# SparkFun_Soil_Moisture_Sensor.net
KiCad netlist of a schematic drawn in EAGLE
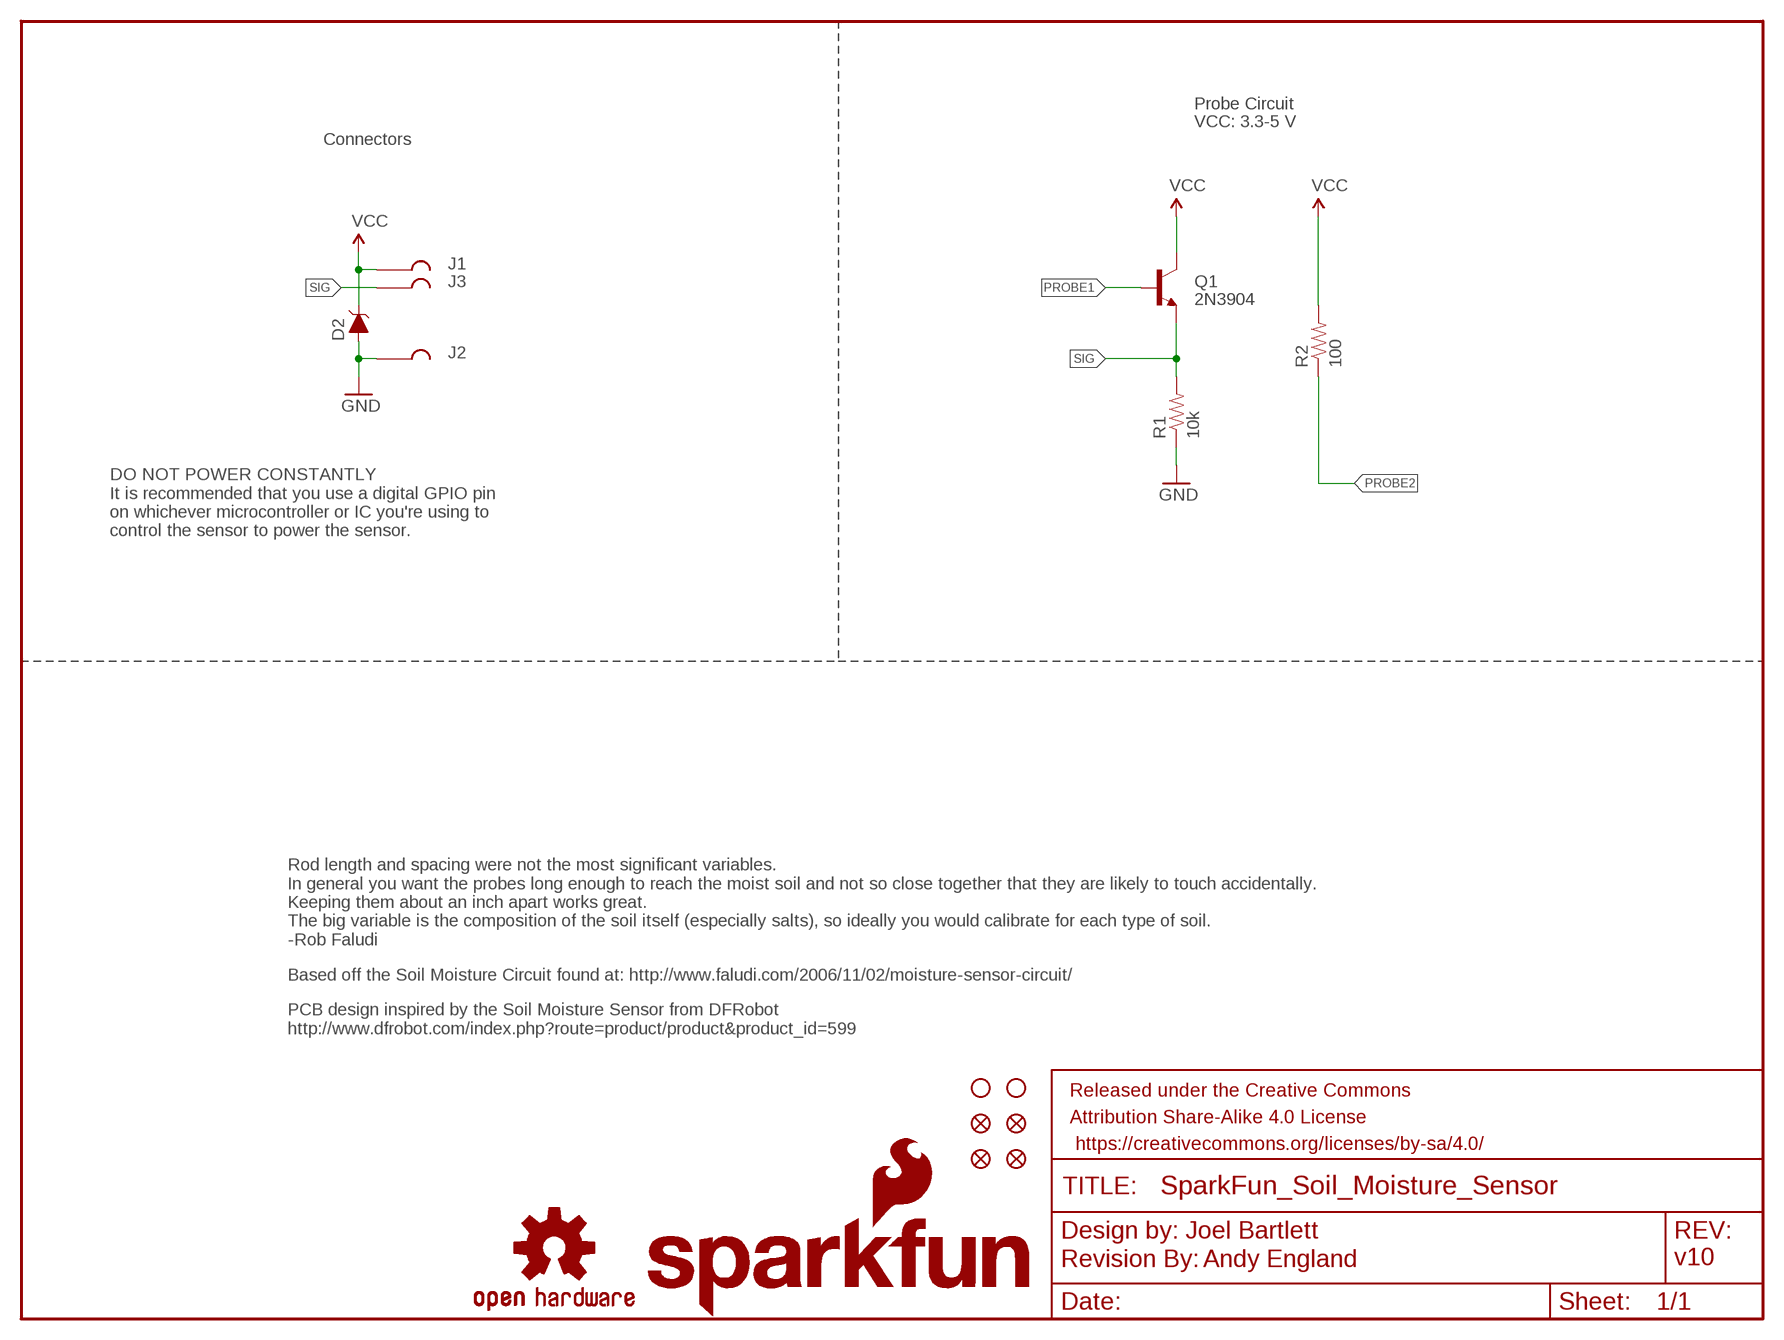
[diagram p0: schematic, sheet 1]

(export (version "E")
  (design (tool "Eeschema 10.0.6"))
  (components
    (comp (ref "D2")
      (value "3.6V")
      (footprint "eagle-import:SOD-323")
      (libsource (lib "eagle-import") (part "DIODE-ZENER-BZT52C3V6S"))
    )
    (comp (ref "FID1")
      (value "FIDUCIAL1X2")
      (footprint "eagle-import:FIDUCIAL-1X2")
      (libsource (lib "eagle-import") (part "FIDUCIAL1X2"))
    )
    (comp (ref "FID2")
      (value "FIDUCIAL1X2")
      (footprint "eagle-import:FIDUCIAL-1X2")
      (libsource (lib "eagle-import") (part "FIDUCIAL1X2"))
    )
    (comp (ref "FID3")
      (value "FIDUCIAL1X2")
      (footprint "eagle-import:FIDUCIAL-1X2")
      (libsource (lib "eagle-import") (part "FIDUCIAL1X2"))
    )
    (comp (ref "FID4")
      (value "FIDUCIAL1X2")
      (footprint "eagle-import:FIDUCIAL-1X2")
      (libsource (lib "eagle-import") (part "FIDUCIAL1X2"))
    )
    (comp (ref "FRAME1")
      (value "FRAME-LETTER")
      (footprint "eagle-import:CREATIVE_COMMONS")
      (fields
        (field (name "DESIGNER") "Joel Bartlett")
        (field (name "VERSION") "v10")
        (field (name "DESIGNER_1") "Joel Bartlett")
      )
      (libsource (lib "eagle-import") (part "FRAME-LETTER"))
    )
    (comp (ref "J1")
      (value "GATORGATOR_MINI")
      (footprint "eagle-import:GATOR_MINI")
      (libsource (lib "eagle-import") (part "GATORGATOR_MINI"))
    )
    (comp (ref "J2")
      (value "GATORGATOR_MINI")
      (footprint "eagle-import:GATOR_MINI")
      (libsource (lib "eagle-import") (part "GATORGATOR_MINI"))
    )
    (comp (ref "J3")
      (value "GATORGATOR_MINI")
      (footprint "eagle-import:GATOR_MINI")
      (libsource (lib "eagle-import") (part "GATORGATOR_MINI"))
    )
    (comp (ref "LOGO1")
      (value "SFE_LOGO_NAME_FLAME.1_INCH")
      (footprint "eagle-import:SFE_LOGO_NAME_FLAME_.1")
      (libsource (lib "eagle-import") (part "SFE_LOGO_NAME_FLAME.1_INCH"))
    )
    (comp (ref "LOGO2")
      (value "OSHW-LOGOS")
      (footprint "eagle-import:OSHW-LOGO-S")
      (libsource (lib "eagle-import") (part "OSHW-LOGOS"))
    )
    (comp (ref "LOGO3")
      (value "REVISION")
      (footprint "eagle-import:REVISION")
      (libsource (lib "eagle-import") (part "REVISION"))
    )
    (comp (ref "Q1")
      (value "2N3904")
      (footprint "eagle-import:SOT23-3@1")
      (libsource (lib "eagle-import") (part "TRANSISTOR_NPNMMBT2222A"))
    )
    (comp (ref "R1")
      (value "10k")
      (footprint "eagle-import:0603")
      (libsource (lib "eagle-import") (part "10KOHM-0603-1/10W-1%"))
    )
    (comp (ref "R2")
      (value "100")
      (footprint "eagle-import:0603")
      (libsource (lib "eagle-import") (part "100OHM-0603-1/10W-1%"))
    )
    (comp (ref "STANDOFF1")
      (value "STAND-OFF")
      (footprint "eagle-import:STAND-OFF")
      (libsource (lib "eagle-import") (part "STAND-OFF"))
    )
    (comp (ref "STANDOFF2")
      (value "STAND-OFF")
      (footprint "eagle-import:STAND-OFF")
      (libsource (lib "eagle-import") (part "STAND-OFF"))
    )
  )
  (nets
    (net (code "1") (name "GND") (class "Default")
      (node (ref "D2") (pin "A") (pinfunction "A_A") (pintype "passive"))
      (node (ref "J2") (pin "P$2") (pinfunction "P$1_P$2") (pintype "bidirectional"))
      (node (ref "R1") (pin "1") (pinfunction "1_1") (pintype "passive"))
    )
    (net (code "2") (name "PROBE1") (class "Default")
      (node (ref "Q1") (pin "1") (pinfunction "B_1") (pintype "passive"))
    )
    (net (code "3") (name "PROBE2") (class "Default")
      (node (ref "R2") (pin "1") (pinfunction "1_1") (pintype "passive"))
    )
    (net (code "4") (name "SIG") (class "Default")
      (node (ref "J3") (pin "P$2") (pinfunction "P$1_P$2") (pintype "bidirectional"))
      (node (ref "Q1") (pin "2") (pinfunction "E_2") (pintype "passive"))
      (node (ref "R1") (pin "2") (pinfunction "2_2") (pintype "passive"))
    )
    (net (code "5") (name "VCC") (class "Default")
      (node (ref "D2") (pin "C") (pinfunction "C_C") (pintype "passive"))
      (node (ref "J1") (pin "P$2") (pinfunction "P$1_P$2") (pintype "bidirectional"))
      (node (ref "Q1") (pin "3") (pinfunction "C_3") (pintype "passive"))
      (node (ref "R2") (pin "2") (pinfunction "2_2") (pintype "passive"))
    )
  )
)
